# Sheet1.net
KiCad netlist of a schematic drawn in Altium Designer
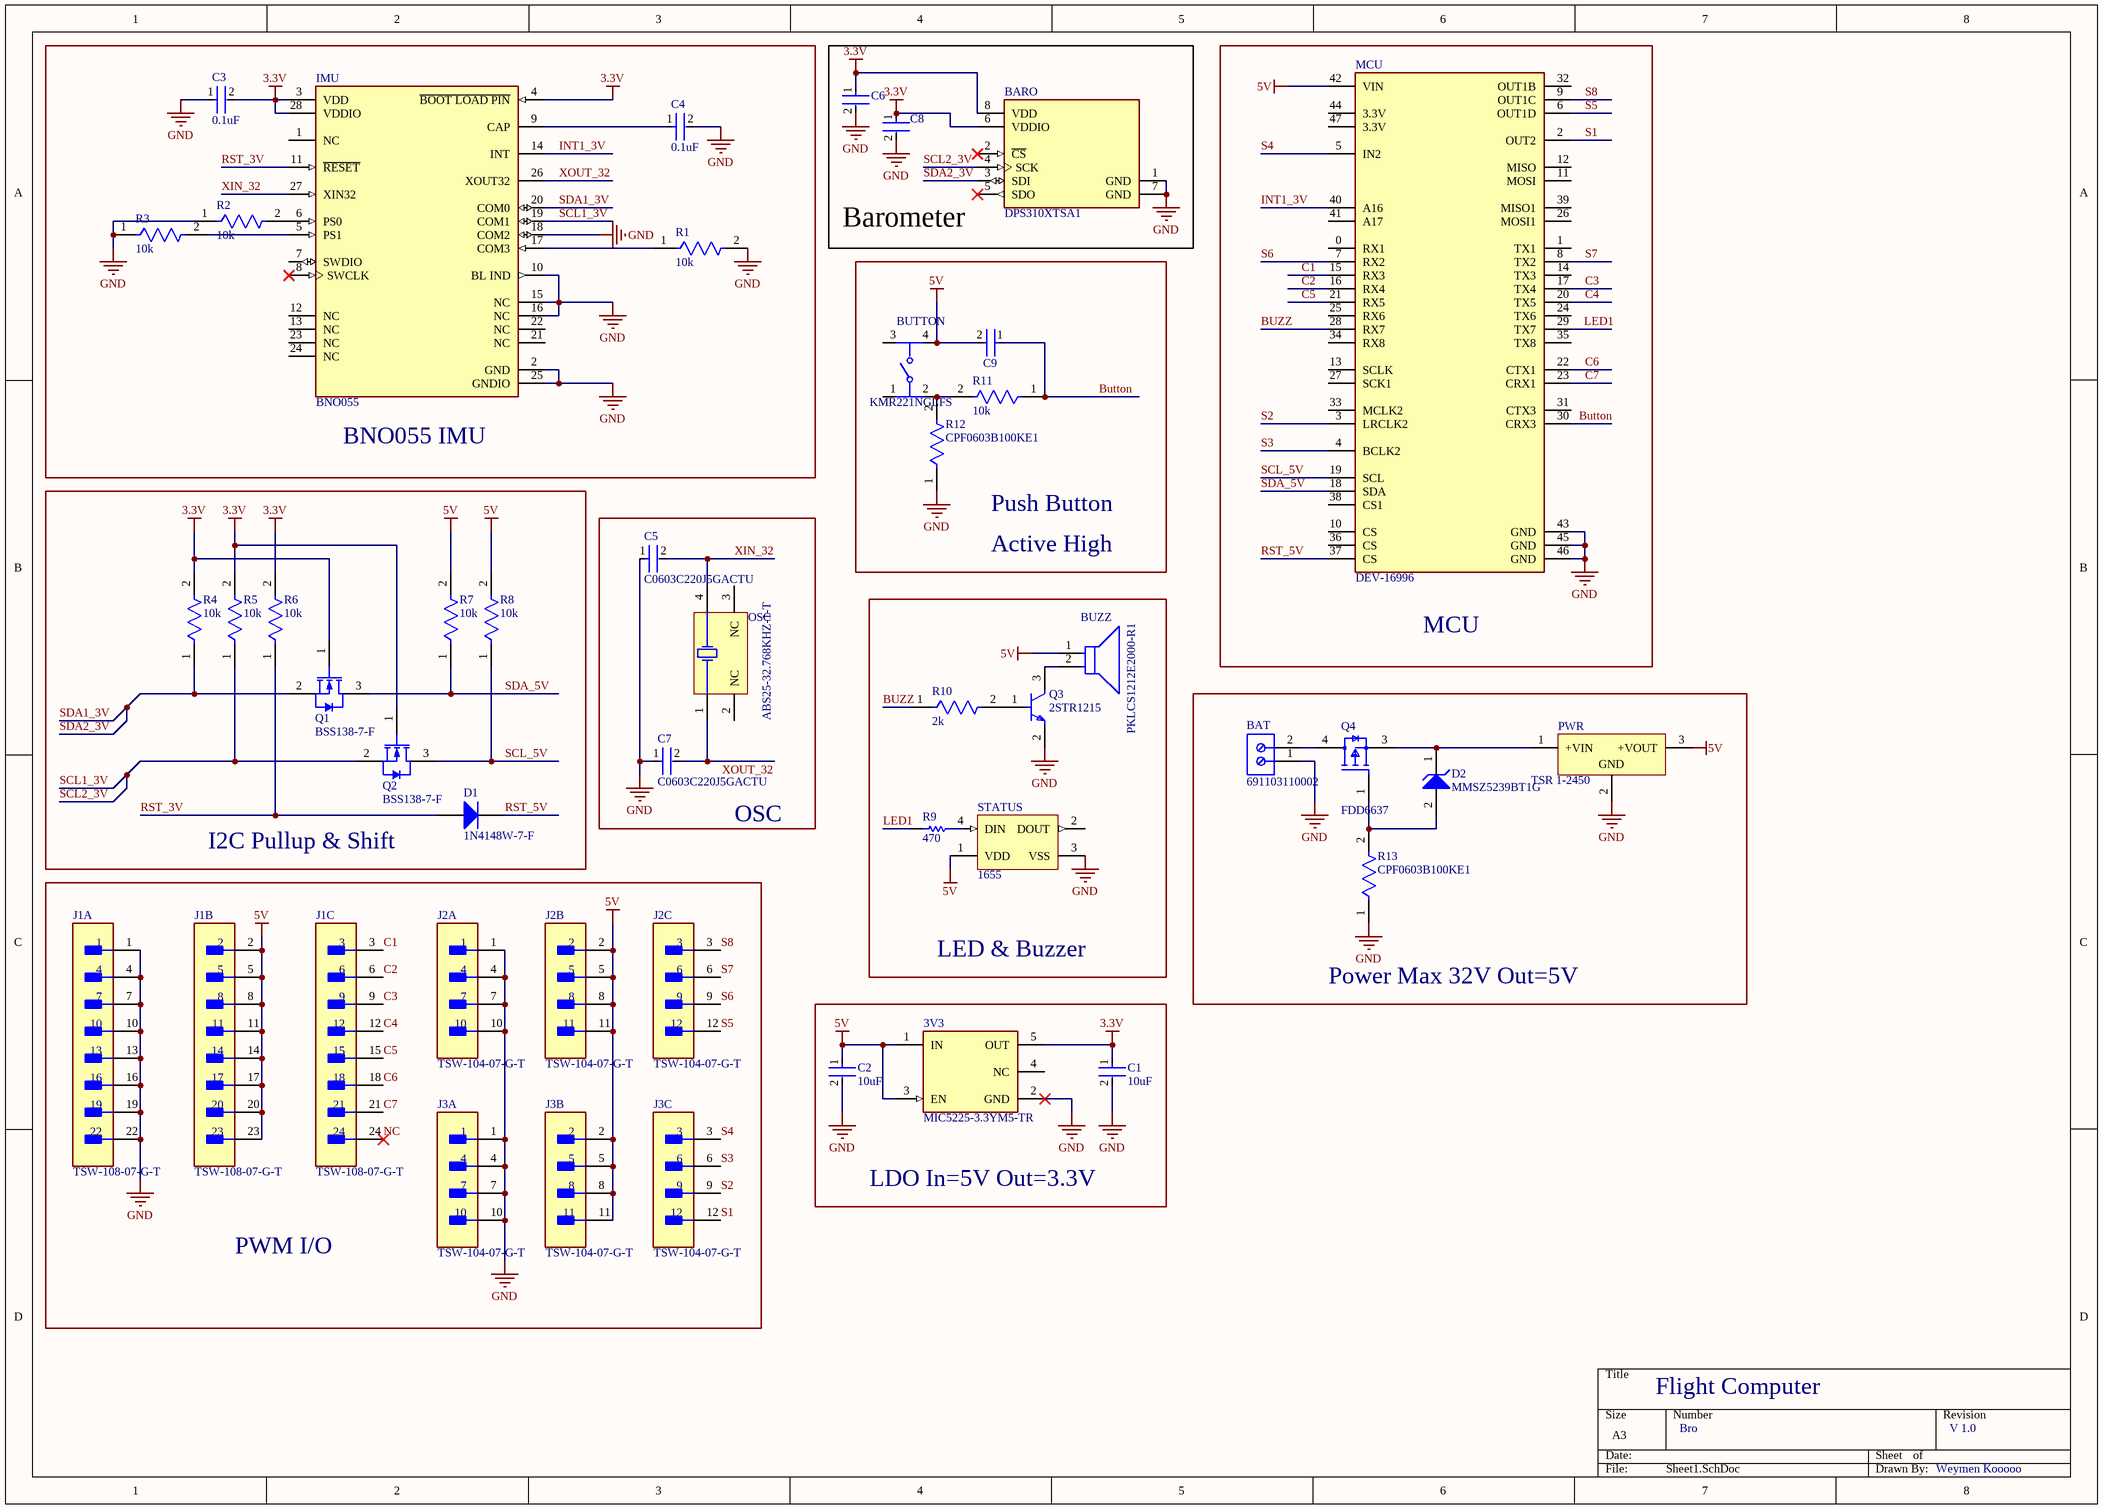
[diagram p0: Sheet1.SchDoc]

(export (version "E")
  (design (tool "Eeschema 10.0.6"))
  (components
    (comp (ref "3V3")
      (value "MIC5225-3.3YM5-TR")
      (footprint "FP-SOT23-5LD-PL-1-MFG")
      (description "IC REG LINEAR 3.3V 150MA SOT23-5")
      (fields
        (field (name "MANUFACTURER") "Microchip Technology")
        (field (name "OCTOPART") "https://octopart.com/mic5225-3.3ym5-tr-microchip-66802280")
      )
      (libsource (lib "Altium Content Vault") (part "19d222bb1c978341ac53d4d0acc2020"))
    )
    (comp (ref "BARO")
      (value "DPS310XTSA1")
      (footprint "FP-PG-VLGA-8-MFG")
      (description "SENSOR PRESSURE CAPACITIVE")
      (libsource (lib "Altium Content Vault") (part "2f9b9cb14541673a24f46422860e4ec"))
    )
    (comp (ref "BAT")
      (value "691103110002")
      (footprint "691103110002")
      (description "Series 1031 - 3.50 mm Horizontal Entry Modular with Pressure Clamp WR-TBL, 2 pin")
      (fields (field (name "MANUFACTURER") "Wurth Elektronik") (field (name "PUBLISHER") "WurthElektronik"))
      (libsource (lib "Altium Content Vault") (part "WE-CN-1P-F-TB2"))
    )
    (comp (ref "BUTTON")
      (value "KMR221NGLFS")
      (footprint "FP-KMR221NGLFS-0")
      (description "SWITCH TACTILE SPST-NO 0.05A 32V")
      (fields
        (field (name "MANUFACTURER") "C&K")
        (field (name "OCTOPART") "https://octopart.com/kmr221nglfs-c%26k+components-7203802")
      )
      (libsource (lib "Altium Content Vault") (part "b8895f3f4cefb76e1819d2863dba89b"))
    )
    (comp (ref "BUZZ")
      (value "PKLCS1212E2000-R1")
      (footprint "FP-PKLCS1212E2000-R1-MFG")
      (description "AUDIO PIEZO TRANSDUCER 12.5V SMD")
      (fields
        (field (name "MANUFACTURER") "Murata")
        (field (name "OCTOPART") "https://octopart.com/pklcs1212e2000-r1-murata-7123179")
      )
      (libsource (lib "Altium Content Vault") (part "5f581d31613f872430949aa526fd155"))
    )
    (comp (ref "C1")
      (value "10uF")
      (footprint "FP-GRM188-0_1-e0_2_0_55-IPC_A")
      (description "Chip Multilayer Ceramic Capacitors for General Purpose, 0603, 10uF, X5R, 15%, 20%, 6.3V")
      (fields (field (name "VOLTAGE") "6.3V") (field (name "TOLERANCE") "20%"))
      (libsource (lib "Altium Content Vault") (part "02cd4be3c70576c341d710602a673aa"))
    )
    (comp (ref "C2")
      (value "10uF")
      (footprint "FP-GRM188-0_1-e0_2_0_55-IPC_A")
      (description "Chip Multilayer Ceramic Capacitors for General Purpose, 0603, 10uF, X5R, 15%, 20%, 6.3V")
      (fields (field (name "VOLTAGE") "6.3V") (field (name "TOLERANCE") "20%"))
      (libsource (lib "Altium Content Vault") (part "02cd4be3c70576c341d710602a673aa"))
    )
    (comp (ref "C3")
      (value "0.1uF")
      (footprint "FP-C0603C-CF-MFG")
      (description "CAP CER 0.1UF 50V X7R 0603")
      (fields (field (name "TOLERANCE") "0.1") (field (name "MANUFACTURER") "KEMET"))
      (libsource (lib "Altium Content Vault") (part "b4654b650e69147ec39a6b967a45e02"))
    )
    (comp (ref "C4")
      (value "0.1uF")
      (footprint "FP-C0603C-CF-MFG")
      (description "CAP CER 0.1UF 50V X7R 0603")
      (fields (field (name "TOLERANCE") "0.1") (field (name "MANUFACTURER") "KEMET"))
      (libsource (lib "Altium Content Vault") (part "b4654b650e69147ec39a6b967a45e02"))
    )
    (comp (ref "C5")
      (value "C0603C220J5GACTU")
      (footprint "FP-C0603C-CF-MFG")
      (description "Cap Ceramic 22pF 50V C0G 5% SMD 0603 125°C Paper T/R")
      (fields (field (name "TOLERANCE") "0.05") (field (name "MANUFACTURER") "KEMET"))
      (libsource (lib "Altium Content Vault") (part "b4654b650e69147ec39a6b967a45e02"))
    )
    (comp (ref "C6")
      (value "CGA3E2X7R1H104K080AA")
      (footprint "FP-CGA3E-0_3-0_1-IPC_A")
      (description "Cap Ceramic 100nF 50V X7R 10% Pad SMD 0603 +125°C Automotive T/R")
      (fields (field (name "TOLERANCE") "10%") (field (name "VOLTAGE") "50V"))
      (libsource (lib "Altium Content Vault") (part "b4654b650e69147ec39a6b967a45e02"))
    )
    (comp (ref "C7")
      (value "C0603C220J5GACTU")
      (footprint "FP-C0603C-CF-MFG")
      (description "Cap Ceramic 22pF 50V C0G 5% SMD 0603 125°C Paper T/R")
      (fields (field (name "TOLERANCE") "0.05") (field (name "MANUFACTURER") "KEMET"))
      (libsource (lib "Altium Content Vault") (part "b4654b650e69147ec39a6b967a45e02"))
    )
    (comp (ref "C8")
      (value "CGA3E2X7R1H104K080AA")
      (footprint "FP-CGA3E-0_3-0_1-IPC_A")
      (description "Cap Ceramic 100nF 50V X7R 10% Pad SMD 0603 +125°C Automotive T/R")
      (fields (field (name "TOLERANCE") "10%") (field (name "VOLTAGE") "50V"))
      (libsource (lib "Altium Content Vault") (part "b4654b650e69147ec39a6b967a45e02"))
    )
    (comp (ref "C9")
      (value "CGA3E2X7R1H104K080AA")
      (footprint "FP-CGA3E-0_3-0_1-IPC_A")
      (description "Cap Ceramic 100nF 50V X7R 10% Pad SMD 0603 +125°C Automotive T/R")
      (fields (field (name "TOLERANCE") "10%") (field (name "VOLTAGE") "50V"))
      (libsource (lib "Altium Content Vault") (part "b4654b650e69147ec39a6b967a45e02"))
    )
    (comp (ref "D1")
      (value "1N4148W-7-F")
      (footprint "DIOD-SOD123-2_V")
      (description "Fast Switching Diode, 100 V, 0.15 A, -65 to 150 degC, 2-Pin?SOD123, RoHS, Tape and Reel")
      (fields (field (name "MANUFACTURER") "DiodesIncorporated"))
      (libsource (lib "Altium Content Vault") (part "D-AK-2"))
    )
    (comp (ref "D2")
      (value "MMSZ5239BT1G")
      (footprint "ONSC-SOD-123-2-425-04_V")
      (description "Zener Voltage Regulator, 500 mW, 2-Pin SOD-123, Pb-Free, Tape and Reel")
      (fields (field (name "MANUFACTURER") "On Semiconductor"))
      (libsource (lib "Altium Content Vault") (part "ONSC-K1A2-2"))
    )
    (comp (ref "IMU")
      (value "BNO055")
      (footprint "FP-BNO055-MFG")
      (description "IMU ACCEL/GYRO/MAG I2C 28LGA")
      (libsource (lib "Altium Content Vault") (part "ba837af00a0b6167256f888b31462b1"))
    )
    (comp (ref "J1")
      (value "TSW-108-07-G-T")
      (footprint "FP-TSW-108-07-G-T-MFG")
      (description "CONN HEADER VERT 24POS 2.54MM")
      (libsource (lib "Altium Content Vault") (part "1970d49fc78c71aba99bcf3589d2fd7"))
    )
    (comp (ref "J2")
      (value "TSW-104-07-G-T")
      (footprint "FP-TSW-104-07-G-T-MFG")
      (description "CONN HEADER VERT 12POS 2.54MM")
      (fields
        (field (name "MANUFACTURER") "Samtec")
        (field (name "OCTOPART") "https://octopart.com/tsw-104-07-g-t-samtec-8296723")
      )
      (libsource (lib "Altium Content Vault") (part "4835ffea529f644fb4232fae0277480"))
    )
    (comp (ref "J3")
      (value "TSW-104-07-G-T")
      (footprint "FP-TSW-104-07-G-T-MFG")
      (description "CONN HEADER VERT 12POS 2.54MM")
      (fields
        (field (name "MANUFACTURER") "Samtec")
        (field (name "OCTOPART") "https://octopart.com/tsw-104-07-g-t-samtec-8296723")
      )
      (libsource (lib "Altium Content Vault") (part "4835ffea529f644fb4232fae0277480"))
    )
    (comp (ref "MCU")
      (value "DEV-16996")
      (footprint "FP-DEV-16996-MFG")
      (description "TEENSY 4.1 (HEADERS)")
      (libsource (lib "Altium Content Vault") (part "080115a1ce54750370cf87ec145ee29"))
    )
    (comp (ref "OSC")
      (value "ABS25-32.768KHZ-1-T")
      (footprint "ABRA-ABS25-4_V")
      (description "Low Frequency Crystal, 32.768 KHz, -40 to 85 degC, 4-Pin SMD, RoHS, Tape and Reel")
      (fields (field (name "MANUFACTURER") "ABRACON") (field (name "TOLERANCE") "10PPM"))
      (libsource (lib "Altium Content Vault") (part "XTAL-1-4-4_A"))
    )
    (comp (ref "PWR")
      (value "TSR 1-2450")
      (footprint "TRACO-SIP-3_V")
      (description "DC/DC converter, 5 VDC, 1000 mA, -40 to 85 degC, 3-Pin SIP, RoHS")
      (fields (field (name "MANUFACTURER") "Tracopower"))
      (libsource (lib "Altium Content Vault") (part "TRACO-TSR1-2450-SIP-3"))
    )
    (comp (ref "Q1")
      (value "BSS138-7-F")
      (footprint "DIOD-SOT23-3_V")
      (description "N-Channel Enhancement Mode Mosfet, 50 V, 0.2 A, -55 to 150 degC, 3-Pin SOT23, RoHS, Tape and Reel")
      (fields (field (name "MANUFACTURER") "Diodes Inc"))
      (libsource (lib "Altium Content Vault") (part "NEMOS-GSD-3"))
    )
    (comp (ref "Q2")
      (value "BSS138-7-F")
      (footprint "DIOD-SOT23-3_V")
      (description "N-Channel Enhancement Mode Mosfet, 50 V, 0.2 A, -55 to 150 degC, 3-Pin SOT23, RoHS, Tape and Reel")
      (fields (field (name "MANUFACTURER") "Diodes Inc"))
      (libsource (lib "Altium Content Vault") (part "NEMOS-GSD-3"))
    )
    (comp (ref "Q3")
      (value "2STR1215")
      (footprint "FP-SOT23_8162275-MFG")
      (description "TRANS NPN 15V 1.5A SOT-23")
      (libsource (lib "Altium Content Vault") (part "b44e953556f554d0102664c7d152cb4"))
    )
    (comp (ref "Q4")
      (value "FDD6637")
      (footprint "FP-369AS-MFG")
      (description "MOSFET P-CH 35V 13A DPAK")
      (fields
        (field (name "OCTOPART") "https://octopart.com/fdd6637-on+semiconductor-84325825")
        (field (name "MANUFACTURER") "ON Semiconductor")
      )
      (libsource (lib "Altium Content Vault") (part "cee2e0b37b8b7601ebfb19aba2d2b4e"))
    )
    (comp (ref "R1")
      (value "10k")
      (footprint "FP-RC0603-0_55-IPC_C")
      (description "RES 10K OHM 1% 1/10W 0603")
      (fields (field (name "TOLERANCE") "1%"))
      (libsource (lib "Altium Content Vault") (part "1029c3af85768c4190bb7ad29bc67b5"))
    )
    (comp (ref "R2")
      (value "10k")
      (footprint "FP-RC0603-0_55-IPC_C")
      (description "RES 10K OHM 1% 1/10W 0603")
      (fields (field (name "TOLERANCE") "1%"))
      (libsource (lib "Altium Content Vault") (part "1029c3af85768c4190bb7ad29bc67b5"))
    )
    (comp (ref "R3")
      (value "10k")
      (footprint "FP-RC0603-0_55-IPC_C")
      (description "RES 10K OHM 1% 1/10W 0603")
      (fields (field (name "TOLERANCE") "1%"))
      (libsource (lib "Altium Content Vault") (part "1029c3af85768c4190bb7ad29bc67b5"))
    )
    (comp (ref "R4")
      (value "10k")
      (footprint "FP-RC0603-0_55-IPC_C")
      (description "RES 10K OHM 1% 1/10W 0603")
      (fields (field (name "TOLERANCE") "1%"))
      (libsource (lib "Altium Content Vault") (part "1029c3af85768c4190bb7ad29bc67b5"))
    )
    (comp (ref "R5")
      (value "10k")
      (footprint "FP-RC0603-0_55-IPC_C")
      (description "RES 10K OHM 1% 1/10W 0603")
      (fields (field (name "TOLERANCE") "1%"))
      (libsource (lib "Altium Content Vault") (part "1029c3af85768c4190bb7ad29bc67b5"))
    )
    (comp (ref "R6")
      (value "10k")
      (footprint "FP-RC0603-0_55-IPC_C")
      (description "RES 10K OHM 1% 1/10W 0603")
      (fields (field (name "TOLERANCE") "1%"))
      (libsource (lib "Altium Content Vault") (part "1029c3af85768c4190bb7ad29bc67b5"))
    )
    (comp (ref "R7")
      (value "10k")
      (footprint "FP-RC0603-0_55-IPC_C")
      (description "RES 10K OHM 1% 1/10W 0603")
      (fields (field (name "TOLERANCE") "1%"))
      (libsource (lib "Altium Content Vault") (part "1029c3af85768c4190bb7ad29bc67b5"))
    )
    (comp (ref "R8")
      (value "10k")
      (footprint "FP-RC0603-0_55-IPC_C")
      (description "RES 10K OHM 1% 1/10W 0603")
      (fields (field (name "TOLERANCE") "1%"))
      (libsource (lib "Altium Content Vault") (part "1029c3af85768c4190bb7ad29bc67b5"))
    )
    (comp (ref "R9")
      (value "470")
      (footprint "RESC1608X55X30NL15T15")
      (fields (field (name "PART NUMBER") "ERJ-3GEYJ471V") (field (name "MANUFACTURER") "Panasonic"))
      (libsource (lib "Altium Content Vault") (part "RES"))
    )
    (comp (ref "R10")
      (value "2k")
      (footprint "FP-ERA3A-IPC_C")
      (description "RES SMD 2K OHM 0.1% 1/10W 0603")
      (fields (field (name "TOLERANCE") "0.1%"))
      (libsource (lib "Altium Content Vault") (part "1029c3af85768c4190bb7ad29bc67b5"))
    )
    (comp (ref "R11")
      (value "10k")
      (footprint "FP-RC0603-0_55-IPC_C")
      (description "RES 10K OHM 1% 1/10W 0603")
      (fields (field (name "TOLERANCE") "1%"))
      (libsource (lib "Altium Content Vault") (part "1029c3af85768c4190bb7ad29bc67b5"))
    )
    (comp (ref "R12")
      (value "CPF0603B100KE1")
      (footprint "FP-CPF0603-MFG")
      (description "RES SMD 100KΩ 0.1% 1/16W 0603")
      (fields
        (field (name "MANUFACTURER") "TE Connectivity")
        (field (name "OCTOPART") "https://octopart.com/cpf0603b100ke1-te+connectivity-9539443")
      )
      (libsource (lib "Altium Content Vault") (part "1029c3af85768c4190bb7ad29bc67b5"))
    )
    (comp (ref "R13")
      (value "CPF0603B100KE1")
      (footprint "FP-CPF0603-MFG")
      (description "RES SMD 100KΩ 0.1% 1/16W 0603")
      (fields
        (field (name "MANUFACTURER") "TE Connectivity")
        (field (name "OCTOPART") "https://octopart.com/cpf0603b100ke1-te+connectivity-9539443")
      )
      (libsource (lib "Altium Content Vault") (part "1029c3af85768c4190bb7ad29bc67b5"))
    )
    (comp (ref "STATUS")
      (value "1655")
      (footprint "ADA-RGB-1655_V")
      (fields (field (name "MANUFACTURER") "Adafruit-Industries-LLC"))
      (libsource (lib "Altium Content Vault") (part "ADA-RGB-1655-4"))
    )
  )
  (nets
    (net (code "1") (name "/BUZZ") (class "Default")
      (node (ref "MCU") (pin "28") (pinfunction "RX7_28") (pintype "passive"))
      (node (ref "R10") (pin "1") (pinfunction "1_1") (pintype "passive"))
    )
    (net (code "2") (name "/Button") (class "Default")
      (node (ref "C9") (pin "1") (pinfunction "1_1") (pintype "passive"))
      (node (ref "MCU") (pin "30") (pinfunction "CRX3_30") (pintype "passive"))
      (node (ref "R11") (pin "1") (pinfunction "1_1") (pintype "passive"))
    )
    (net (code "3") (name "/C1") (class "Default")
      (node (ref "J1") (pin "3") (pinfunction "3_3") (pintype "passive"))
      (node (ref "MCU") (pin "15") (pinfunction "RX3_15") (pintype "passive"))
    )
    (net (code "4") (name "/C2") (class "Default")
      (node (ref "J1") (pin "6") (pinfunction "6_6") (pintype "passive"))
      (node (ref "MCU") (pin "16") (pinfunction "RX4_16") (pintype "passive"))
    )
    (net (code "5") (name "/C3") (class "Default")
      (node (ref "J1") (pin "9") (pinfunction "9_9") (pintype "passive"))
      (node (ref "MCU") (pin "17") (pinfunction "TX4_17") (pintype "passive"))
    )
    (net (code "6") (name "/C4") (class "Default")
      (node (ref "J1") (pin "12") (pinfunction "12_12") (pintype "passive"))
      (node (ref "MCU") (pin "20") (pinfunction "TX5_20") (pintype "passive"))
    )
    (net (code "7") (name "/C5") (class "Default")
      (node (ref "J1") (pin "15") (pinfunction "15_15") (pintype "passive"))
      (node (ref "MCU") (pin "21") (pinfunction "RX5_21") (pintype "passive"))
    )
    (net (code "8") (name "/C6") (class "Default")
      (node (ref "J1") (pin "18") (pinfunction "18_18") (pintype "passive"))
      (node (ref "MCU") (pin "22") (pinfunction "CTX1_22") (pintype "passive"))
    )
    (net (code "9") (name "/C7") (class "Default")
      (node (ref "J1") (pin "21") (pinfunction "21_21") (pintype "passive"))
      (node (ref "MCU") (pin "23") (pinfunction "CRX1_23") (pintype "passive"))
    )
    (net (code "10") (name "/INT1_3V") (class "Default")
      (node (ref "IMU") (pin "14") (pinfunction "INT_14") (pintype "passive"))
      (node (ref "MCU") (pin "40") (pinfunction "A16_40") (pintype "passive"))
    )
    (net (code "11") (name "/LED1") (class "Default")
      (node (ref "MCU") (pin "29") (pinfunction "TX7_29") (pintype "passive"))
      (node (ref "R9") (pin "1") (pinfunction "1_1") (pintype "passive"))
    )
    (net (code "12") (name "/NC") (class "Default")
      (node (ref "J1") (pin "24") (pinfunction "24_24") (pintype "passive+no_connect"))
    )
    (net (code "13") (name "/RST_3V") (class "Default")
      (node (ref "D1") (pin "1") (pinfunction "A_1") (pintype "passive"))
      (node (ref "IMU") (pin "11") (pinfunction "~{RESET}_11") (pintype "input"))
      (node (ref "R6") (pin "1") (pinfunction "1_1") (pintype "passive"))
    )
    (net (code "14") (name "/RST_5V") (class "Default")
      (node (ref "D1") (pin "2") (pinfunction "K_2") (pintype "passive"))
      (node (ref "MCU") (pin "37") (pinfunction "CS_37") (pintype "passive"))
    )
    (net (code "15") (name "/S1") (class "Default")
      (node (ref "J3") (pin "12") (pinfunction "12_12") (pintype "passive"))
      (node (ref "MCU") (pin "2") (pinfunction "OUT2_2") (pintype "passive"))
    )
    (net (code "16") (name "/S2") (class "Default")
      (node (ref "J3") (pin "9") (pinfunction "9_9") (pintype "passive"))
      (node (ref "MCU") (pin "3") (pinfunction "LRCLK2_3") (pintype "passive"))
    )
    (net (code "17") (name "/S3") (class "Default")
      (node (ref "J3") (pin "6") (pinfunction "6_6") (pintype "passive"))
      (node (ref "MCU") (pin "4") (pinfunction "BCLK2_4") (pintype "passive"))
    )
    (net (code "18") (name "/S4") (class "Default")
      (node (ref "J3") (pin "3") (pinfunction "3_3") (pintype "passive"))
      (node (ref "MCU") (pin "5") (pinfunction "IN2_5") (pintype "passive"))
    )
    (net (code "19") (name "/S5") (class "Default")
      (node (ref "J2") (pin "12") (pinfunction "12_12") (pintype "passive"))
      (node (ref "MCU") (pin "6") (pinfunction "OUT1D_6") (pintype "passive"))
    )
    (net (code "20") (name "/S6") (class "Default")
      (node (ref "J2") (pin "9") (pinfunction "9_9") (pintype "passive"))
      (node (ref "MCU") (pin "7") (pinfunction "RX2_7") (pintype "passive"))
    )
    (net (code "21") (name "/S7") (class "Default")
      (node (ref "J2") (pin "6") (pinfunction "6_6") (pintype "passive"))
      (node (ref "MCU") (pin "8") (pinfunction "TX2_8") (pintype "passive"))
    )
    (net (code "22") (name "/S8") (class "Default")
      (node (ref "J2") (pin "3") (pinfunction "3_3") (pintype "passive"))
      (node (ref "MCU") (pin "9") (pinfunction "OUT1C_9") (pintype "passive"))
    )
    (net (code "23") (name "/SCL1_3V") (class "Default")
      (node (ref "BARO") (pin "4") (pinfunction "SCK_4") (pintype "input"))
      (node (ref "IMU") (pin "19") (pinfunction "COM1_19") (pintype "bidirectional"))
      (node (ref "Q2") (pin "2") (pinfunction "S_2") (pintype "passive"))
      (node (ref "R5") (pin "1") (pinfunction "1_1") (pintype "passive"))
    )
    (net (code "24") (name "/SCL_5V") (class "Default")
      (node (ref "MCU") (pin "19") (pinfunction "SCL_19") (pintype "passive"))
      (node (ref "Q2") (pin "3") (pinfunction "D_3") (pintype "passive"))
      (node (ref "R8") (pin "1") (pinfunction "1_1") (pintype "passive"))
    )
    (net (code "25") (name "/SDA1_3V") (class "Default")
      (node (ref "BARO") (pin "3") (pinfunction "SDI_3") (pintype "bidirectional"))
      (node (ref "IMU") (pin "20") (pinfunction "COM0_20") (pintype "bidirectional"))
      (node (ref "Q1") (pin "2") (pinfunction "S_2") (pintype "passive"))
      (node (ref "R4") (pin "1") (pinfunction "1_1") (pintype "passive"))
    )
    (net (code "26") (name "/SDA_5V") (class "Default")
      (node (ref "MCU") (pin "18") (pinfunction "SDA_18") (pintype "passive"))
      (node (ref "Q1") (pin "3") (pinfunction "D_3") (pintype "passive"))
      (node (ref "R7") (pin "1") (pinfunction "1_1") (pintype "passive"))
    )
    (net (code "27") (name "/XIN_32") (class "Default")
      (node (ref "C5") (pin "2") (pinfunction "2_2") (pintype "passive"))
      (node (ref "IMU") (pin "27") (pinfunction "XIN32_27") (pintype "input"))
      (node (ref "OSC") (pin "4") (pinfunction "X2_4") (pintype "passive"))
    )
    (net (code "28") (name "/XOUT_32") (class "Default")
      (node (ref "C7") (pin "2") (pinfunction "2_2") (pintype "passive"))
      (node (ref "IMU") (pin "26") (pinfunction "XOUT32_26") (pintype "passive"))
      (node (ref "OSC") (pin "1") (pinfunction "X1_1") (pintype "passive"))
    )
    (net (code "29") (name "3.3V") (class "Default")
      (node (ref "3V3") (pin "5") (pinfunction "OUT_5") (pintype "power_in"))
      (node (ref "BARO") (pin "6") (pinfunction "VDDIO_6") (pintype "power_in"))
      (node (ref "BARO") (pin "8") (pinfunction "VDD_8") (pintype "power_in"))
      (node (ref "C1") (pin "1") (pinfunction "1_1") (pintype "passive"))
      (node (ref "C3") (pin "2") (pinfunction "2_2") (pintype "passive"))
      (node (ref "C6") (pin "1") (pinfunction "1_1") (pintype "passive"))
      (node (ref "C8") (pin "1") (pinfunction "1_1") (pintype "passive"))
      (node (ref "IMU") (pin "28") (pinfunction "VDDIO_28") (pintype "power_in"))
      (node (ref "IMU") (pin "3") (pinfunction "VDD_3") (pintype "power_in"))
      (node (ref "IMU") (pin "4") (pinfunction "~{BOOT_LOAD_PIN}_4") (pintype "input"))
      (node (ref "Q1") (pin "1") (pinfunction "G_1") (pintype "passive"))
      (node (ref "Q2") (pin "1") (pinfunction "G_1") (pintype "passive"))
      (node (ref "R4") (pin "2") (pinfunction "2_2") (pintype "passive"))
      (node (ref "R5") (pin "2") (pinfunction "2_2") (pintype "passive"))
      (node (ref "R6") (pin "2") (pinfunction "2_2") (pintype "passive"))
    )
    (net (code "30") (name "5V") (class "Default")
      (node (ref "3V3") (pin "1") (pinfunction "IN_1") (pintype "power_in"))
      (node (ref "3V3") (pin "3") (pinfunction "EN_3") (pintype "input"))
      (node (ref "BUTTON") (pin "4") (pinfunction "4_4") (pintype "passive"))
      (node (ref "BUZZ") (pin "1") (pinfunction "1_1") (pintype "passive"))
      (node (ref "C2") (pin "1") (pinfunction "1_1") (pintype "passive"))
      (node (ref "C9") (pin "2") (pinfunction "2_2") (pintype "passive"))
      (node (ref "J1") (pin "11") (pinfunction "11_11") (pintype "passive"))
      (node (ref "J1") (pin "14") (pinfunction "14_14") (pintype "passive"))
      (node (ref "J1") (pin "17") (pinfunction "17_17") (pintype "passive"))
      (node (ref "J1") (pin "2") (pinfunction "2_2") (pintype "passive"))
      (node (ref "J1") (pin "20") (pinfunction "20_20") (pintype "passive"))
      (node (ref "J1") (pin "23") (pinfunction "23_23") (pintype "passive"))
      (node (ref "J1") (pin "5") (pinfunction "5_5") (pintype "passive"))
      (node (ref "J1") (pin "8") (pinfunction "8_8") (pintype "passive"))
      (node (ref "J2") (pin "11") (pinfunction "11_11") (pintype "passive"))
      (node (ref "J2") (pin "2") (pinfunction "2_2") (pintype "passive"))
      (node (ref "J2") (pin "5") (pinfunction "5_5") (pintype "passive"))
      (node (ref "J2") (pin "8") (pinfunction "8_8") (pintype "passive"))
      (node (ref "J3") (pin "11") (pinfunction "11_11") (pintype "passive"))
      (node (ref "J3") (pin "2") (pinfunction "2_2") (pintype "passive"))
      (node (ref "J3") (pin "5") (pinfunction "5_5") (pintype "passive"))
      (node (ref "J3") (pin "8") (pinfunction "8_8") (pintype "passive"))
      (node (ref "MCU") (pin "42") (pinfunction "VIN_42") (pintype "passive"))
      (node (ref "PWR") (pin "3") (pinfunction "+VOUT_3") (pintype "power_in"))
      (node (ref "R7") (pin "2") (pinfunction "2_2") (pintype "passive"))
      (node (ref "R8") (pin "2") (pinfunction "2_2") (pintype "passive"))
      (node (ref "STATUS") (pin "1") (pinfunction "VDD_1") (pintype "power_in"))
    )
    (net (code "31") (name "GND") (class "Default")
      (node (ref "3V3") (pin "2") (pinfunction "GND_2") (pintype "power_in"))
      (node (ref "BARO") (pin "1") (pinfunction "GND_1") (pintype "power_in"))
      (node (ref "BARO") (pin "7") (pinfunction "GND_7") (pintype "power_in"))
      (node (ref "BAT") (pin "1") (pinfunction "1_1") (pintype "passive"))
      (node (ref "C1") (pin "2") (pinfunction "2_2") (pintype "passive"))
      (node (ref "C2") (pin "2") (pinfunction "2_2") (pintype "passive"))
      (node (ref "C3") (pin "1") (pinfunction "1_1") (pintype "passive"))
      (node (ref "C4") (pin "2") (pinfunction "2_2") (pintype "passive"))
      (node (ref "C5") (pin "1") (pinfunction "1_1") (pintype "passive"))
      (node (ref "C6") (pin "2") (pinfunction "2_2") (pintype "passive"))
      (node (ref "C7") (pin "1") (pinfunction "1_1") (pintype "passive"))
      (node (ref "C8") (pin "2") (pinfunction "2_2") (pintype "passive"))
      (node (ref "IMU") (pin "10") (pinfunction "BL_IND_10") (pintype "output"))
      (node (ref "IMU") (pin "15") (pinfunction "NC_15") (pintype "passive"))
      (node (ref "IMU") (pin "16") (pinfunction "NC_16") (pintype "passive"))
      (node (ref "IMU") (pin "18") (pinfunction "COM2_18") (pintype "bidirectional"))
      (node (ref "IMU") (pin "2") (pinfunction "GND_2") (pintype "power_in"))
      (node (ref "IMU") (pin "25") (pinfunction "GNDIO_25") (pintype "power_in"))
      (node (ref "J1") (pin "1") (pinfunction "1_1") (pintype "passive"))
      (node (ref "J1") (pin "10") (pinfunction "10_10") (pintype "passive"))
      (node (ref "J1") (pin "13") (pinfunction "13_13") (pintype "passive"))
      (node (ref "J1") (pin "16") (pinfunction "16_16") (pintype "passive"))
      (node (ref "J1") (pin "19") (pinfunction "19_19") (pintype "passive"))
      (node (ref "J1") (pin "22") (pinfunction "22_22") (pintype "passive"))
      (node (ref "J1") (pin "4") (pinfunction "4_4") (pintype "passive"))
      (node (ref "J1") (pin "7") (pinfunction "7_7") (pintype "passive"))
      (node (ref "J2") (pin "1") (pinfunction "1_1") (pintype "passive"))
      (node (ref "J2") (pin "10") (pinfunction "10_10") (pintype "passive"))
      (node (ref "J2") (pin "4") (pinfunction "4_4") (pintype "passive"))
      (node (ref "J2") (pin "7") (pinfunction "7_7") (pintype "passive"))
      (node (ref "J3") (pin "1") (pinfunction "1_1") (pintype "passive"))
      (node (ref "J3") (pin "10") (pinfunction "10_10") (pintype "passive"))
      (node (ref "J3") (pin "4") (pinfunction "4_4") (pintype "passive"))
      (node (ref "J3") (pin "7") (pinfunction "7_7") (pintype "passive"))
      (node (ref "MCU") (pin "43") (pinfunction "GND_43") (pintype "passive"))
      (node (ref "MCU") (pin "45") (pinfunction "GND_45") (pintype "passive"))
      (node (ref "MCU") (pin "46") (pinfunction "GND_46") (pintype "passive"))
      (node (ref "PWR") (pin "2") (pinfunction "GND_2") (pintype "power_in"))
      (node (ref "Q3") (pin "2") (pinfunction "E_2") (pintype "passive"))
      (node (ref "R1") (pin "2") (pinfunction "2_2") (pintype "passive"))
      (node (ref "R12") (pin "1") (pinfunction "1_1") (pintype "passive"))
      (node (ref "R13") (pin "1") (pinfunction "1_1") (pintype "passive"))
      (node (ref "R2") (pin "1") (pinfunction "1_1") (pintype "passive"))
      (node (ref "R3") (pin "1") (pinfunction "1_1") (pintype "passive"))
      (node (ref "STATUS") (pin "3") (pinfunction "VSS_3") (pintype "power_in"))
    )
    (net (code "32") (name "Net-(BUTTON-Pad2)") (class "Default")
      (node (ref "BUTTON") (pin "2") (pinfunction "2_2") (pintype "passive"))
      (node (ref "R11") (pin "2") (pinfunction "2_2") (pintype "passive"))
      (node (ref "R12") (pin "2") (pinfunction "2_2") (pintype "passive"))
    )
    (net (code "33") (name "Net-(D2-A)") (class "Default")
      (node (ref "D2") (pin "2") (pinfunction "A_2") (pintype "passive"))
      (node (ref "Q4") (pin "1") (pinfunction "G_1") (pintype "passive"))
      (node (ref "R13") (pin "2") (pinfunction "2_2") (pintype "passive"))
    )
    (net (code "34") (name "Net-(D2-K)") (class "Default")
      (node (ref "D2") (pin "1") (pinfunction "K_1") (pintype "passive"))
      (node (ref "PWR") (pin "1") (pinfunction "+VIN_1") (pintype "power_in"))
      (node (ref "Q4") (pin "3") (pinfunction "S_3") (pintype "passive"))
    )
    (net (code "35") (name "Net-(IMU-CAP)") (class "Default")
      (node (ref "C4") (pin "1") (pinfunction "1_1") (pintype "passive"))
      (node (ref "IMU") (pin "9") (pinfunction "CAP_9") (pintype "passive"))
    )
    (net (code "36") (name "Net-(IMU-COM3)") (class "Default")
      (node (ref "IMU") (pin "17") (pinfunction "COM3_17") (pintype "input"))
      (node (ref "R1") (pin "1") (pinfunction "1_1") (pintype "passive"))
    )
    (net (code "37") (name "Net-(IMU-PS0)") (class "Default")
      (node (ref "IMU") (pin "6") (pinfunction "PS0_6") (pintype "input"))
      (node (ref "R2") (pin "2") (pinfunction "2_2") (pintype "passive"))
    )
    (net (code "38") (name "Net-(IMU-PS1)") (class "Default")
      (node (ref "IMU") (pin "5") (pinfunction "PS1_5") (pintype "input"))
      (node (ref "R3") (pin "2") (pinfunction "2_2") (pintype "passive"))
    )
    (net (code "39") (name "Net-(Q3-B)") (class "Default")
      (node (ref "Q3") (pin "1") (pinfunction "B_1") (pintype "passive"))
      (node (ref "R10") (pin "2") (pinfunction "2_2") (pintype "passive"))
    )
    (net (code "40") (name "Net-(Q3-C)") (class "Default")
      (node (ref "BUZZ") (pin "2") (pinfunction "2_2") (pintype "passive"))
      (node (ref "Q3") (pin "3") (pinfunction "C_3") (pintype "passive"))
    )
    (net (code "41") (name "Net-(Q4-D)") (class "Default")
      (node (ref "BAT") (pin "2") (pinfunction "2_2") (pintype "passive"))
      (node (ref "Q4") (pin "4") (pinfunction "D_4") (pintype "passive"))
    )
    (net (code "42") (name "Net-(STATUS-DIN)") (class "Default")
      (node (ref "R9") (pin "2") (pinfunction "2_2") (pintype "passive"))
      (node (ref "STATUS") (pin "4") (pinfunction "DIN_4") (pintype "input"))
    )
    (net (code "43") (name "unconnected-(3V3-NC-Pad4)") (class "Default")
      (node (ref "3V3") (pin "4") (pinfunction "NC_4") (pintype "passive"))
    )
    (net (code "44") (name "unconnected-(BARO-SDO-Pad5)") (class "Default")
      (node (ref "BARO") (pin "5") (pinfunction "SDO_5") (pintype "output+no_connect"))
    )
    (net (code "45") (name "unconnected-(BARO-~{CS}-Pad2)") (class "Default")
      (node (ref "BARO") (pin "2") (pinfunction "~{CS}_2") (pintype "input+no_connect"))
    )
    (net (code "46") (name "unconnected-(BUTTON-Pad1)") (class "Default")
      (node (ref "BUTTON") (pin "1") (pinfunction "1_1") (pintype "passive"))
    )
    (net (code "47") (name "unconnected-(BUTTON-Pad3)") (class "Default")
      (node (ref "BUTTON") (pin "3") (pinfunction "3_3") (pintype "passive"))
    )
    (net (code "48") (name "unconnected-(IMU-NC-Pad1)") (class "Default")
      (node (ref "IMU") (pin "1") (pinfunction "NC_1") (pintype "passive"))
    )
    (net (code "49") (name "unconnected-(IMU-NC-Pad12)") (class "Default")
      (node (ref "IMU") (pin "12") (pinfunction "NC_12") (pintype "passive"))
    )
    (net (code "50") (name "unconnected-(IMU-NC-Pad13)") (class "Default")
      (node (ref "IMU") (pin "13") (pinfunction "NC_13") (pintype "passive"))
    )
    (net (code "51") (name "unconnected-(IMU-NC-Pad21)") (class "Default")
      (node (ref "IMU") (pin "21") (pinfunction "NC_21") (pintype "passive"))
    )
    (net (code "52") (name "unconnected-(IMU-NC-Pad22)") (class "Default")
      (node (ref "IMU") (pin "22") (pinfunction "NC_22") (pintype "passive"))
    )
    (net (code "53") (name "unconnected-(IMU-NC-Pad23)") (class "Default")
      (node (ref "IMU") (pin "23") (pinfunction "NC_23") (pintype "passive"))
    )
    (net (code "54") (name "unconnected-(IMU-NC-Pad24)") (class "Default")
      (node (ref "IMU") (pin "24") (pinfunction "NC_24") (pintype "passive"))
    )
    (net (code "55") (name "unconnected-(IMU-SWCLK-Pad8)") (class "Default")
      (node (ref "IMU") (pin "8") (pinfunction "SWCLK_8") (pintype "input+no_connect"))
    )
    (net (code "56") (name "unconnected-(IMU-SWDIO-Pad7)") (class "Default")
      (node (ref "IMU") (pin "7") (pinfunction "SWDIO_7") (pintype "bidirectional"))
    )
    (net (code "57") (name "unconnected-(MCU-3.3V-Pad44)") (class "Default")
      (node (ref "MCU") (pin "44") (pinfunction "3.3V_44") (pintype "passive"))
    )
    (net (code "58") (name "unconnected-(MCU-3.3V-Pad47)") (class "Default")
      (node (ref "MCU") (pin "47") (pinfunction "3.3V_47") (pintype "passive"))
    )
    (net (code "59") (name "unconnected-(MCU-A17-Pad41)") (class "Default")
      (node (ref "MCU") (pin "41") (pinfunction "A17_41") (pintype "passive"))
    )
    (net (code "60") (name "unconnected-(MCU-CS-Pad10)") (class "Default")
      (node (ref "MCU") (pin "10") (pinfunction "CS_10") (pintype "passive"))
    )
    (net (code "61") (name "unconnected-(MCU-CS-Pad36)") (class "Default")
      (node (ref "MCU") (pin "36") (pinfunction "CS_36") (pintype "passive"))
    )
    (net (code "62") (name "unconnected-(MCU-CS1-Pad38)") (class "Default")
      (node (ref "MCU") (pin "38") (pinfunction "CS1_38") (pintype "passive"))
    )
    (net (code "63") (name "unconnected-(MCU-CTX3-Pad31)") (class "Default")
      (node (ref "MCU") (pin "31") (pinfunction "CTX3_31") (pintype "passive"))
    )
    (net (code "64") (name "unconnected-(MCU-MCLK2-Pad33)") (class "Default")
      (node (ref "MCU") (pin "33") (pinfunction "MCLK2_33") (pintype "passive"))
    )
    (net (code "65") (name "unconnected-(MCU-MISO-Pad12)") (class "Default")
      (node (ref "MCU") (pin "12") (pinfunction "MISO_12") (pintype "passive"))
    )
    (net (code "66") (name "unconnected-(MCU-MISO1-Pad39)") (class "Default")
      (node (ref "MCU") (pin "39") (pinfunction "MISO1_39") (pintype "passive"))
    )
    (net (code "67") (name "unconnected-(MCU-MOSI-Pad11)") (class "Default")
      (node (ref "MCU") (pin "11") (pinfunction "MOSI_11") (pintype "passive"))
    )
    (net (code "68") (name "unconnected-(MCU-MOSI1-Pad26)") (class "Default")
      (node (ref "MCU") (pin "26") (pinfunction "MOSI1_26") (pintype "passive"))
    )
    (net (code "69") (name "unconnected-(MCU-OUT1B-Pad32)") (class "Default")
      (node (ref "MCU") (pin "32") (pinfunction "OUT1B_32") (pintype "passive"))
    )
    (net (code "70") (name "unconnected-(MCU-RX1-Pad0)") (class "Default")
      (node (ref "MCU") (pin "0") (pinfunction "RX1_0") (pintype "passive"))
    )
    (net (code "71") (name "unconnected-(MCU-RX6-Pad25)") (class "Default")
      (node (ref "MCU") (pin "25") (pinfunction "RX6_25") (pintype "passive"))
    )
    (net (code "72") (name "unconnected-(MCU-RX8-Pad34)") (class "Default")
      (node (ref "MCU") (pin "34") (pinfunction "RX8_34") (pintype "passive"))
    )
    (net (code "73") (name "unconnected-(MCU-SCK1-Pad27)") (class "Default")
      (node (ref "MCU") (pin "27") (pinfunction "SCK1_27") (pintype "passive"))
    )
    (net (code "74") (name "unconnected-(MCU-SCLK-Pad13)") (class "Default")
      (node (ref "MCU") (pin "13") (pinfunction "SCLK_13") (pintype "passive"))
    )
    (net (code "75") (name "unconnected-(MCU-TX1-Pad1)") (class "Default")
      (node (ref "MCU") (pin "1") (pinfunction "TX1_1") (pintype "passive"))
    )
    (net (code "76") (name "unconnected-(MCU-TX3-Pad14)") (class "Default")
      (node (ref "MCU") (pin "14") (pinfunction "TX3_14") (pintype "passive"))
    )
    (net (code "77") (name "unconnected-(MCU-TX6-Pad24)") (class "Default")
      (node (ref "MCU") (pin "24") (pinfunction "TX6_24") (pintype "passive"))
    )
    (net (code "78") (name "unconnected-(MCU-TX8-Pad35)") (class "Default")
      (node (ref "MCU") (pin "35") (pinfunction "TX8_35") (pintype "passive"))
    )
    (net (code "79") (name "unconnected-(OSC-NC-Pad2)") (class "Default")
      (node (ref "OSC") (pin "2") (pinfunction "NC_2") (pintype "passive"))
    )
    (net (code "80") (name "unconnected-(OSC-NC-Pad3)") (class "Default")
      (node (ref "OSC") (pin "3") (pinfunction "NC_3") (pintype "passive"))
    )
    (net (code "81") (name "unconnected-(STATUS-DOUT-Pad2)") (class "Default")
      (node (ref "STATUS") (pin "2") (pinfunction "DOUT_2") (pintype "output"))
    )
  )
)
